# adapter.net
KiCad netlist of a schematic drawn in EAGLE
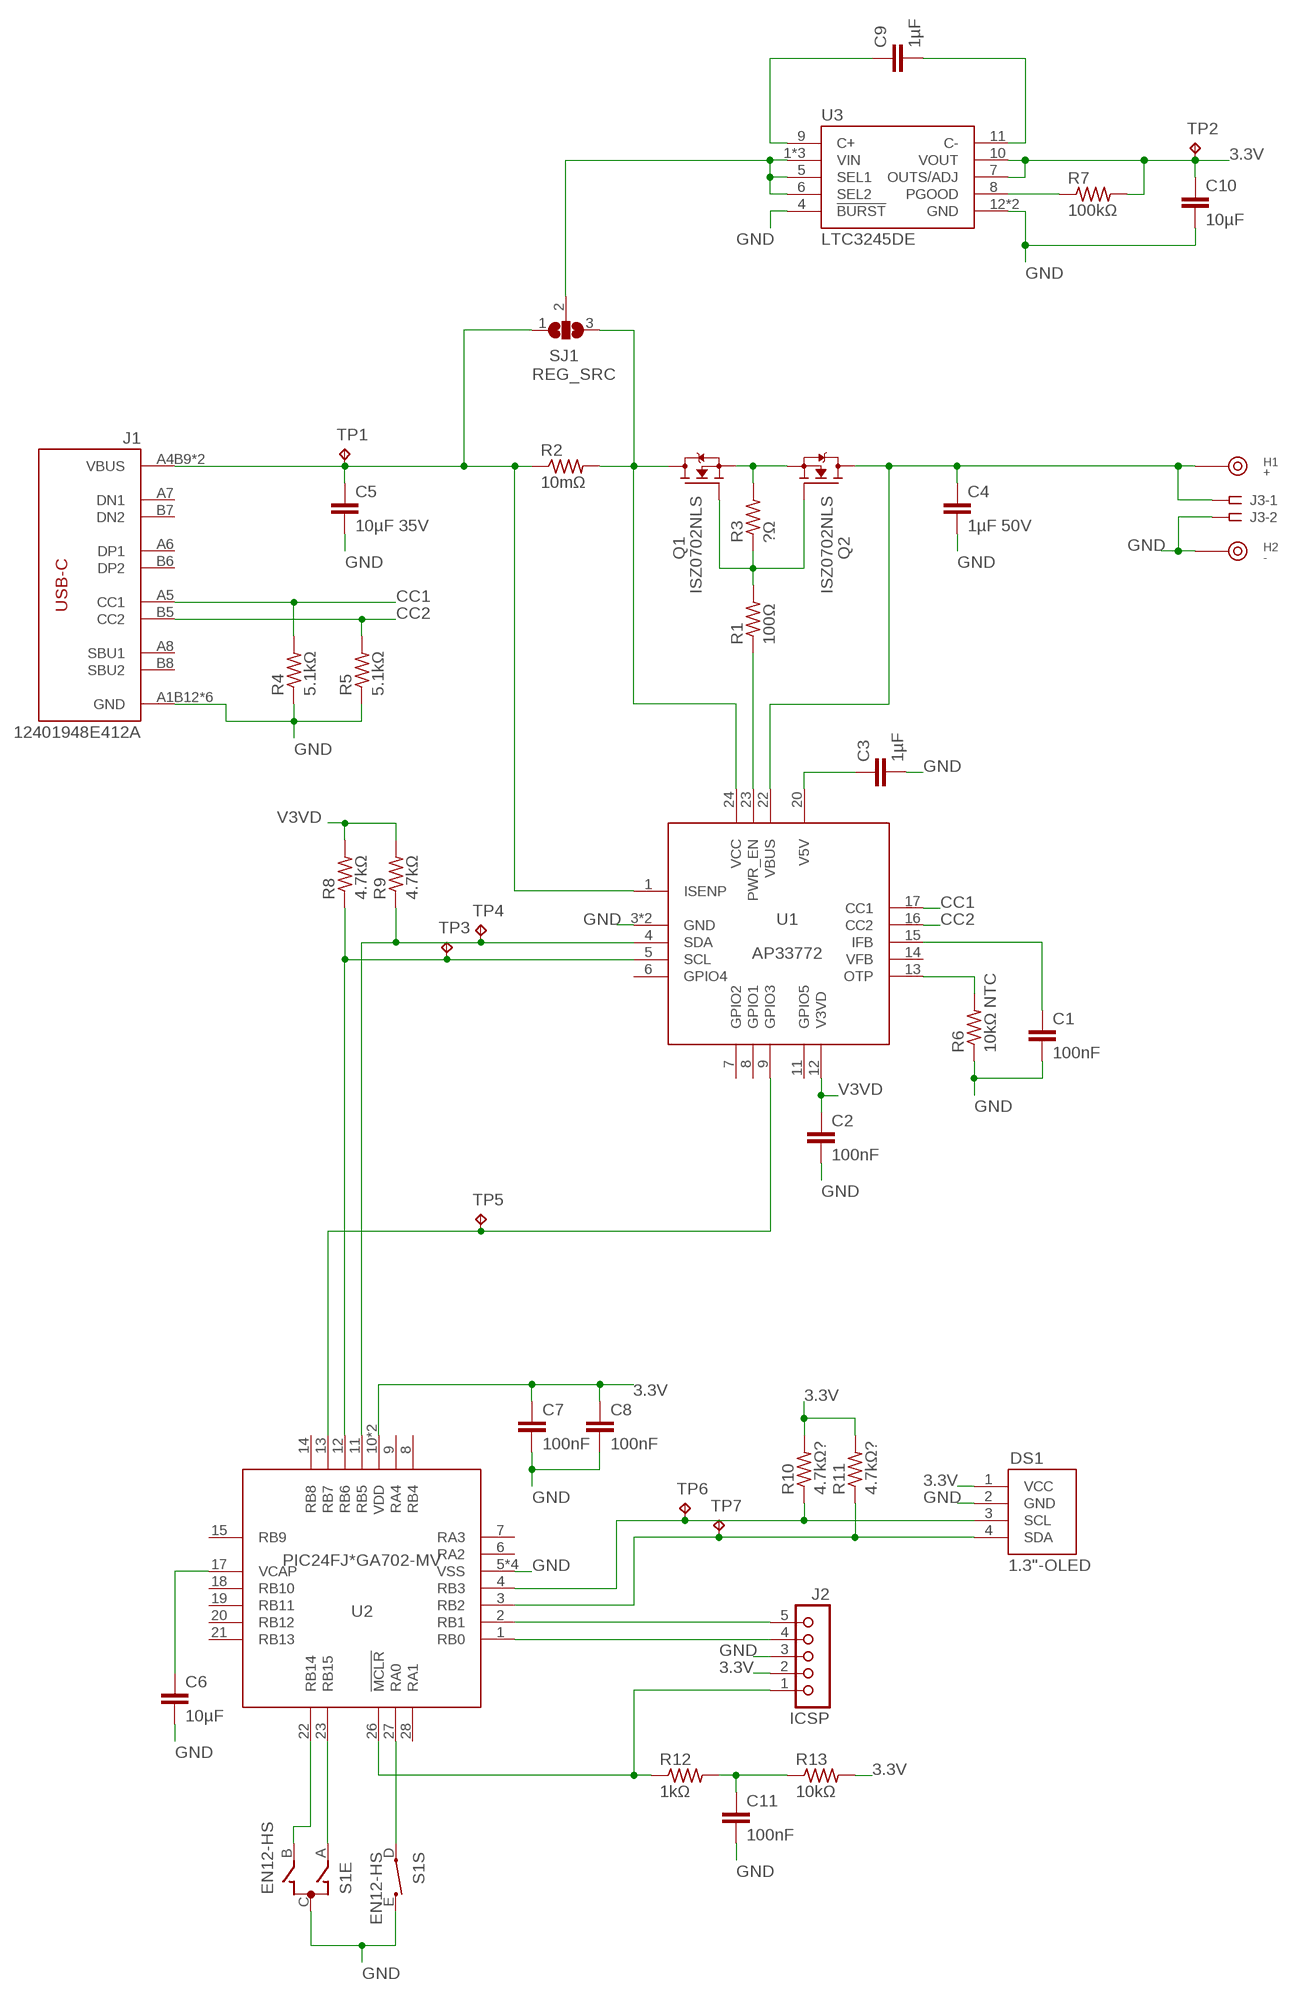
[diagram p0: schematic, sheet 1]

(export (version "E")
  (design (tool "Eeschema 10.0.6"))
  (components
    (comp (ref "C1")
      (value "100nF")
      (footprint "eagle-import:C0603")
      (libsource (lib "eagle-import") (part "C-EUC0603"))
    )
    (comp (ref "C2")
      (value "100nF")
      (footprint "eagle-import:C0603")
      (libsource (lib "eagle-import") (part "C-EUC0603"))
    )
    (comp (ref "C3")
      (value "1µF")
      (footprint "eagle-import:C0603")
      (libsource (lib "eagle-import") (part "C-EUC0603"))
    )
    (comp (ref "C4")
      (value "1µF 50V")
      (footprint "eagle-import:C0603")
      (libsource (lib "eagle-import") (part "C-EUC0603"))
    )
    (comp (ref "C5")
      (value "10µF 35V")
      (footprint "eagle-import:C1206")
      (libsource (lib "eagle-import") (part "C-EUC1206"))
    )
    (comp (ref "C6")
      (value "10µF")
      (footprint "eagle-import:C0805")
      (libsource (lib "eagle-import") (part "C-EUC0805"))
    )
    (comp (ref "C7")
      (value "100nF")
      (footprint "eagle-import:C0603")
      (libsource (lib "eagle-import") (part "C-EUC0603"))
    )
    (comp (ref "C8")
      (value "100nF")
      (footprint "eagle-import:C0603")
      (libsource (lib "eagle-import") (part "C-EUC0603"))
    )
    (comp (ref "C9")
      (value "1µF")
      (footprint "eagle-import:C0603")
      (libsource (lib "eagle-import") (part "C-EUC0603"))
    )
    (comp (ref "C10")
      (value "10µF")
      (footprint "eagle-import:C0805")
      (libsource (lib "eagle-import") (part "C-EUC0805"))
    )
    (comp (ref "C11")
      (value "100nF")
      (footprint "eagle-import:C0603")
      (libsource (lib "eagle-import") (part "C-EUC0603"))
    )
    (comp (ref "DS1")
      (value "1.3\"-OLED")
      (footprint "eagle-import:1.3_-OLED")
      (libsource (lib "eagle-import") (part "1.3{dblquote}-OLED"))
    )
    (comp (ref "H1")
      (value "+")
      (footprint "eagle-import:78614015360")
      (libsource (lib "eagle-import") (part "78614015360"))
    )
    (comp (ref "H2")
      (value "-")
      (footprint "eagle-import:78614015360")
      (libsource (lib "eagle-import") (part "78614015360"))
    )
    (comp (ref "J1")
      (value "12401948E412A")
      (footprint "eagle-import:12401948E412A")
      (libsource (lib "eagle-import") (part "12401948E412A"))
    )
    (comp (ref "J2")
      (value "ICSP")
      (footprint "eagle-import:5PIN-1.27")
      (libsource (lib "eagle-import") (part "5PIN-1.27"))
    )
    (comp (ref "J3")
      (value "SSW-102-02-G-S-RA")
      (footprint "eagle-import:SSW-102-02-G-S-RA")
      (fields (field (name "MF") "Samtec Inc."))
      (libsource (lib "eagle-import") (part "SSW-102-02-G-S-RA"))
    )
    (comp (ref "Q1")
      (value "ISZ0702NLS")
      (footprint "eagle-import:TSDSON-8")
      (libsource (lib "eagle-import") (part "TSDSON-8-N-MOSFET"))
    )
    (comp (ref "Q2")
      (value "ISZ0702NLS")
      (footprint "eagle-import:TSDSON-8")
      (libsource (lib "eagle-import") (part "TSDSON-8-N-MOSFET"))
    )
    (comp (ref "R1")
      (value "100Ω")
      (footprint "eagle-import:R0603")
      (libsource (lib "eagle-import") (part "R-US_R0603"))
    )
    (comp (ref "R2")
      (value "10mΩ")
      (footprint "eagle-import:R1206")
      (libsource (lib "eagle-import") (part "R-US_R1206"))
    )
    (comp (ref "R3")
      (value "?Ω")
      (footprint "eagle-import:R0603")
      (libsource (lib "eagle-import") (part "R-US_R0603"))
    )
    (comp (ref "R4")
      (value "5.1kΩ")
      (footprint "eagle-import:R0603")
      (libsource (lib "eagle-import") (part "R-US_R0603"))
    )
    (comp (ref "R5")
      (value "5.1kΩ")
      (footprint "eagle-import:R0603")
      (libsource (lib "eagle-import") (part "R-US_R0603"))
    )
    (comp (ref "R6")
      (value "10kΩ NTC")
      (footprint "eagle-import:R0603")
      (libsource (lib "eagle-import") (part "R-US_R0603"))
    )
    (comp (ref "R7")
      (value "100kΩ")
      (footprint "eagle-import:R0603")
      (libsource (lib "eagle-import") (part "R-US_R0603"))
    )
    (comp (ref "R8")
      (value "4.7kΩ")
      (footprint "eagle-import:R0603")
      (libsource (lib "eagle-import") (part "R-US_R0603"))
    )
    (comp (ref "R9")
      (value "4.7kΩ")
      (footprint "eagle-import:R0603")
      (libsource (lib "eagle-import") (part "R-US_R0603"))
    )
    (comp (ref "R10")
      (value "4.7kΩ?")
      (footprint "eagle-import:R0603")
      (libsource (lib "eagle-import") (part "R-US_R0603"))
    )
    (comp (ref "R11")
      (value "4.7kΩ?")
      (footprint "eagle-import:R0603")
      (libsource (lib "eagle-import") (part "R-US_R0603"))
    )
    (comp (ref "R12")
      (value "1kΩ")
      (footprint "eagle-import:R0603")
      (libsource (lib "eagle-import") (part "R-US_R0603"))
    )
    (comp (ref "R13")
      (value "10kΩ")
      (footprint "eagle-import:R0603")
      (libsource (lib "eagle-import") (part "R-US_R0603"))
    )
    (comp (ref "S1")
      (value "EN12-HS")
      (footprint "eagle-import:EN12-HS")
      (libsource (lib "eagle-import") (part "EN12-HS"))
    )
    (comp (ref "SJ1")
      (value "REG_SRC")
      (footprint "eagle-import:SJ_2")
      (libsource (lib "eagle-import") (part "SJ2W"))
    )
    (comp (ref "TP1")
      (value "RCU-0(J)")
      (footprint "eagle-import:TP_0603_JOINED")
      (libsource (lib "eagle-import") (part "RCU-0(J)"))
    )
    (comp (ref "TP2")
      (value "RCU-0(J)")
      (footprint "eagle-import:TP_0603_JOINED")
      (libsource (lib "eagle-import") (part "RCU-0(J)"))
    )
    (comp (ref "TP3")
      (value "RCU-0(J)")
      (footprint "eagle-import:TP_0603_JOINED")
      (libsource (lib "eagle-import") (part "RCU-0(J)"))
    )
    (comp (ref "TP4")
      (value "RCU-0(J)")
      (footprint "eagle-import:TP_0603_JOINED")
      (libsource (lib "eagle-import") (part "RCU-0(J)"))
    )
    (comp (ref "TP5")
      (value "RCU-0(J)")
      (footprint "eagle-import:TP_0603_JOINED")
      (libsource (lib "eagle-import") (part "RCU-0(J)"))
    )
    (comp (ref "TP6")
      (value "RCU-0(J)")
      (footprint "eagle-import:TP_0603_JOINED")
      (libsource (lib "eagle-import") (part "RCU-0(J)"))
    )
    (comp (ref "TP7")
      (value "RCU-0(J)")
      (footprint "eagle-import:TP_0603_JOINED")
      (libsource (lib "eagle-import") (part "RCU-0(J)"))
    )
    (comp (ref "U1")
      (value "AP33772")
      (footprint "eagle-import:QFN24-4X4")
      (libsource (lib "eagle-import") (part "AP33772"))
    )
    (comp (ref "U2")
      (value "PIC24FJ*GA702-MV")
      (footprint "eagle-import:UQFN28_4X4MM")
      (libsource (lib "eagle-import") (part "PIC24FJGA702-MV"))
    )
    (comp (ref "U3")
      (value "LTC3245DE")
      (footprint "eagle-import:DFN12")
      (libsource (lib "eagle-import") (part "LTC3245DE"))
    )
  )
  (nets
    (net (code "1") (name "/3.3V") (class "Default")
      (node (ref "C10") (pin "1") (pinfunction "1_1") (pintype "passive"))
      (node (ref "C7") (pin "1") (pinfunction "1_1") (pintype "passive"))
      (node (ref "C8") (pin "1") (pinfunction "1_1") (pintype "passive"))
      (node (ref "DS1") (pin "1") (pinfunction "VCC_1") (pintype "bidirectional"))
      (node (ref "J2") (pin "2") (pinfunction "2_2") (pintype "passive"))
      (node (ref "R10") (pin "2") (pinfunction "2_2") (pintype "passive"))
      (node (ref "R11") (pin "2") (pinfunction "2_2") (pintype "passive"))
      (node (ref "R13") (pin "2") (pinfunction "2_2") (pintype "passive"))
      (node (ref "R7") (pin "2") (pinfunction "2_2") (pintype "passive"))
      (node (ref "TP2") (pin "1") (pinfunction "TP_1") (pintype "input"))
      (node (ref "U2") (pin "10") (pinfunction "VDD_10") (pintype "bidirectional"))
      (node (ref "U2") (pin "25") (pinfunction "VDD_25") (pintype "bidirectional"))
      (node (ref "U3") (pin "10") (pinfunction "VOUT_10") (pintype "bidirectional"))
      (node (ref "U3") (pin "7") (pinfunction "OUTS/ADJ_7") (pintype "bidirectional"))
    )
    (net (code "2") (name "/CC1") (class "Default")
      (node (ref "J1") (pin "A5") (pinfunction "CC1_A5") (pintype "bidirectional"))
      (node (ref "R4") (pin "2") (pinfunction "2_2") (pintype "passive"))
      (node (ref "U1") (pin "17") (pinfunction "CC1_17") (pintype "bidirectional"))
    )
    (net (code "3") (name "/CC2") (class "Default")
      (node (ref "J1") (pin "B5") (pinfunction "CC2_B5") (pintype "bidirectional"))
      (node (ref "R5") (pin "2") (pinfunction "2_2") (pintype "passive"))
      (node (ref "U1") (pin "16") (pinfunction "CC2_16") (pintype "bidirectional"))
    )
    (net (code "4") (name "/GND") (class "Default")
      (node (ref "C1") (pin "2") (pinfunction "2_2") (pintype "passive"))
      (node (ref "C10") (pin "2") (pinfunction "2_2") (pintype "passive"))
      (node (ref "C11") (pin "2") (pinfunction "2_2") (pintype "passive"))
      (node (ref "C2") (pin "2") (pinfunction "2_2") (pintype "passive"))
      (node (ref "C3") (pin "2") (pinfunction "2_2") (pintype "passive"))
      (node (ref "C4") (pin "2") (pinfunction "2_2") (pintype "passive"))
      (node (ref "C5") (pin "2") (pinfunction "2_2") (pintype "passive"))
      (node (ref "C6") (pin "2") (pinfunction "2_2") (pintype "passive"))
      (node (ref "C7") (pin "2") (pinfunction "2_2") (pintype "passive"))
      (node (ref "C8") (pin "2") (pinfunction "2_2") (pintype "passive"))
      (node (ref "DS1") (pin "2") (pinfunction "GND_2") (pintype "bidirectional"))
      (node (ref "H2") (pin "M") (pinfunction "P$1_M") (pintype "bidirectional"))
      (node (ref "J1") (pin "A1B12") (pinfunction "GND_A1B12") (pintype "bidirectional"))
      (node (ref "J1") (pin "B1A12") (pinfunction "GND_B1A12") (pintype "bidirectional"))
      (node (ref "J1") (pin "M1") (pinfunction "GND_M1") (pintype "bidirectional"))
      (node (ref "J1") (pin "M2") (pinfunction "GND_M2") (pintype "bidirectional"))
      (node (ref "J1") (pin "M3") (pinfunction "GND_M3") (pintype "bidirectional"))
      (node (ref "J1") (pin "M4") (pinfunction "GND_M4") (pintype "bidirectional"))
      (node (ref "J2") (pin "3") (pinfunction "3_3") (pintype "passive"))
      (node (ref "J3") (pin "2") (pinfunction "1_2") (pintype "passive"))
      (node (ref "R4") (pin "1") (pinfunction "1_1") (pintype "passive"))
      (node (ref "R5") (pin "1") (pinfunction "1_1") (pintype "passive"))
      (node (ref "R6") (pin "1") (pinfunction "1_1") (pintype "passive"))
      (node (ref "S1") (pin "C") (pinfunction "C_C") (pintype "passive"))
      (node (ref "S1") (pin "E") (pinfunction "2_E") (pintype "passive"))
      (node (ref "U1") (pin "3") (pinfunction "GND_3") (pintype "bidirectional"))
      (node (ref "U1") (pin "EXP") (pinfunction "GND_EXP") (pintype "bidirectional"))
      (node (ref "U2") (pin "16") (pinfunction "VSS_16") (pintype "bidirectional"))
      (node (ref "U2") (pin "24") (pinfunction "VSS_24") (pintype "bidirectional"))
      (node (ref "U2") (pin "5") (pinfunction "VSS_5") (pintype "bidirectional"))
      (node (ref "U2") (pin "TH") (pinfunction "VSS_TH") (pintype "bidirectional"))
      (node (ref "U3") (pin "12") (pinfunction "GND_12") (pintype "bidirectional"))
      (node (ref "U3") (pin "4") (pinfunction "~{BURST}_4") (pintype "bidirectional"))
      (node (ref "U3") (pin "EXP") (pinfunction "GND_EXP") (pintype "bidirectional"))
    )
    (net (code "5") (name "/V3VD") (class "Default")
      (node (ref "C2") (pin "1") (pinfunction "1_1") (pintype "passive"))
      (node (ref "R8") (pin "2") (pinfunction "2_2") (pintype "passive"))
      (node (ref "R9") (pin "2") (pinfunction "2_2") (pintype "passive"))
      (node (ref "U1") (pin "12") (pinfunction "V3VD_12") (pintype "bidirectional"))
    )
    (net (code "6") (name "Net-(C11-Pad1)") (class "Default")
      (node (ref "C11") (pin "1") (pinfunction "1_1") (pintype "passive"))
      (node (ref "R12") (pin "2") (pinfunction "2_2") (pintype "passive"))
      (node (ref "R13") (pin "1") (pinfunction "1_1") (pintype "passive"))
    )
    (net (code "7") (name "Net-(DS1-SCL)") (class "Default")
      (node (ref "DS1") (pin "3") (pinfunction "SCL_3") (pintype "bidirectional"))
      (node (ref "R10") (pin "1") (pinfunction "1_1") (pintype "passive"))
      (node (ref "TP6") (pin "1") (pinfunction "TP_1") (pintype "input"))
      (node (ref "U2") (pin "4") (pinfunction "RB3_4") (pintype "bidirectional"))
    )
    (net (code "8") (name "Net-(DS1-SDA)") (class "Default")
      (node (ref "DS1") (pin "4") (pinfunction "SDA_4") (pintype "bidirectional"))
      (node (ref "R11") (pin "1") (pinfunction "1_1") (pintype "passive"))
      (node (ref "TP7") (pin "1") (pinfunction "TP_1") (pintype "input"))
      (node (ref "U2") (pin "3") (pinfunction "RB2_3") (pintype "bidirectional"))
    )
    (net (code "9") (name "Net-(H1-P$1)") (class "Default")
      (node (ref "C4") (pin "1") (pinfunction "1_1") (pintype "passive"))
      (node (ref "H1") (pin "M") (pinfunction "P$1_M") (pintype "bidirectional"))
      (node (ref "J3") (pin "1") (pinfunction "1_1") (pintype "passive"))
      (node (ref "Q2") (pin "5-8") (pinfunction "D_5-8") (pintype "passive"))
      (node (ref "U1") (pin "22") (pinfunction "VBUS_22") (pintype "bidirectional"))
    )
    (net (code "10") (name "Net-(Q1-D)") (class "Default")
      (node (ref "Q1") (pin "5-8") (pinfunction "D_5-8") (pintype "passive"))
      (node (ref "R2") (pin "2") (pinfunction "2_2") (pintype "passive"))
      (node (ref "SJ1") (pin "3") (pinfunction "3_3") (pintype "passive"))
      (node (ref "U1") (pin "24") (pinfunction "VCC_24") (pintype "bidirectional"))
    )
    (net (code "11") (name "Net-(Q1-G)") (class "Default")
      (node (ref "Q1") (pin "4") (pinfunction "G_4") (pintype "passive"))
      (node (ref "Q2") (pin "4") (pinfunction "G_4") (pintype "passive"))
      (node (ref "R1") (pin "2") (pinfunction "2_2") (pintype "passive"))
      (node (ref "R3") (pin "1") (pinfunction "1_1") (pintype "passive"))
    )
    (net (code "12") (name "Net-(Q1-S-Pad1)") (class "Default")
      (node (ref "Q1") (pin "1") (pinfunction "S_1") (pintype "passive"))
      (node (ref "Q1") (pin "2") (pinfunction "S_2") (pintype "passive"))
      (node (ref "Q1") (pin "3") (pinfunction "S_3") (pintype "passive"))
      (node (ref "Q2") (pin "1") (pinfunction "S_1") (pintype "passive"))
      (node (ref "Q2") (pin "2") (pinfunction "S_2") (pintype "passive"))
      (node (ref "Q2") (pin "3") (pinfunction "S_3") (pintype "passive"))
      (node (ref "R3") (pin "2") (pinfunction "2_2") (pintype "passive"))
    )
    (net (code "13") (name "Net-(S1B-1)") (class "Default")
      (node (ref "S1") (pin "D") (pinfunction "1_D") (pintype "passive"))
      (node (ref "U2") (pin "27") (pinfunction "RA0_27") (pintype "bidirectional"))
    )
    (net (code "14") (name "Net-(TP1-TP)") (class "Default")
      (node (ref "C5") (pin "1") (pinfunction "1_1") (pintype "passive"))
      (node (ref "J1") (pin "A4B9") (pinfunction "VBUS_A4B9") (pintype "bidirectional"))
      (node (ref "J1") (pin "B4A9") (pinfunction "VBUS_B4A9") (pintype "bidirectional"))
      (node (ref "R2") (pin "1") (pinfunction "1_1") (pintype "passive"))
      (node (ref "SJ1") (pin "1") (pinfunction "1_1") (pintype "passive"))
      (node (ref "TP1") (pin "1") (pinfunction "TP_1") (pintype "input"))
      (node (ref "U1") (pin "1") (pinfunction "ISENP_1") (pintype "bidirectional"))
    )
    (net (code "15") (name "Net-(TP3-TP)") (class "Default")
      (node (ref "R8") (pin "1") (pinfunction "1_1") (pintype "passive"))
      (node (ref "TP3") (pin "1") (pinfunction "TP_1") (pintype "input"))
      (node (ref "U1") (pin "5") (pinfunction "SCL_5") (pintype "bidirectional"))
      (node (ref "U2") (pin "12") (pinfunction "RB6_12") (pintype "bidirectional"))
    )
    (net (code "16") (name "Net-(TP4-TP)") (class "Default")
      (node (ref "R9") (pin "1") (pinfunction "1_1") (pintype "passive"))
      (node (ref "TP4") (pin "1") (pinfunction "TP_1") (pintype "input"))
      (node (ref "U1") (pin "4") (pinfunction "SDA_4") (pintype "bidirectional"))
      (node (ref "U2") (pin "11") (pinfunction "RB5_11") (pintype "bidirectional"))
    )
    (net (code "17") (name "Net-(TP5-TP)") (class "Default")
      (node (ref "TP5") (pin "1") (pinfunction "TP_1") (pintype "input"))
      (node (ref "U1") (pin "9") (pinfunction "GPIO3_9") (pintype "bidirectional"))
      (node (ref "U2") (pin "13") (pinfunction "RB7_13") (pintype "bidirectional"))
    )
    (net (code "18") (name "Net-(U1-IFB)") (class "Default")
      (node (ref "C1") (pin "1") (pinfunction "1_1") (pintype "passive"))
      (node (ref "U1") (pin "15") (pinfunction "IFB_15") (pintype "bidirectional"))
    )
    (net (code "19") (name "Net-(U1-OTP)") (class "Default")
      (node (ref "R6") (pin "2") (pinfunction "2_2") (pintype "passive"))
      (node (ref "U1") (pin "13") (pinfunction "OTP_13") (pintype "bidirectional"))
    )
    (net (code "20") (name "Net-(U1-PWR_EN)") (class "Default")
      (node (ref "R1") (pin "1") (pinfunction "1_1") (pintype "passive"))
      (node (ref "U1") (pin "23") (pinfunction "PWR_EN_23") (pintype "bidirectional"))
    )
    (net (code "21") (name "Net-(U1-V5V)") (class "Default")
      (node (ref "C3") (pin "1") (pinfunction "1_1") (pintype "passive"))
      (node (ref "U1") (pin "20") (pinfunction "V5V_20") (pintype "bidirectional"))
    )
    (net (code "22") (name "Net-(U2-RB0)") (class "Default")
      (node (ref "J2") (pin "4") (pinfunction "4_4") (pintype "passive"))
      (node (ref "U2") (pin "1") (pinfunction "RB0_1") (pintype "bidirectional"))
    )
    (net (code "23") (name "Net-(U2-RB1)") (class "Default")
      (node (ref "J2") (pin "5") (pinfunction "5_5") (pintype "passive"))
      (node (ref "U2") (pin "2") (pinfunction "RB1_2") (pintype "bidirectional"))
    )
    (net (code "24") (name "Net-(U2-RB14)") (class "Default")
      (node (ref "S1") (pin "B") (pinfunction "B_B") (pintype "passive"))
      (node (ref "U2") (pin "22") (pinfunction "RB14_22") (pintype "bidirectional"))
    )
    (net (code "25") (name "Net-(U2-RB15)") (class "Default")
      (node (ref "S1") (pin "A") (pinfunction "A_A") (pintype "passive"))
      (node (ref "U2") (pin "23") (pinfunction "RB15_23") (pintype "bidirectional"))
    )
    (net (code "26") (name "Net-(U2-VCAP)") (class "Default")
      (node (ref "C6") (pin "1") (pinfunction "1_1") (pintype "passive"))
      (node (ref "U2") (pin "17") (pinfunction "VCAP_17") (pintype "bidirectional"))
    )
    (net (code "27") (name "Net-(U2-~{MCLR})") (class "Default")
      (node (ref "J2") (pin "1") (pinfunction "1_1") (pintype "passive"))
      (node (ref "R12") (pin "1") (pinfunction "1_1") (pintype "passive"))
      (node (ref "U2") (pin "26") (pinfunction "~{MCLR}_26") (pintype "bidirectional"))
    )
    (net (code "28") (name "Net-(U3-C+)") (class "Default")
      (node (ref "C9") (pin "1") (pinfunction "1_1") (pintype "passive"))
      (node (ref "U3") (pin "9") (pinfunction "C+_9") (pintype "bidirectional"))
    )
    (net (code "29") (name "Net-(U3-C-)") (class "Default")
      (node (ref "C9") (pin "2") (pinfunction "2_2") (pintype "passive"))
      (node (ref "U3") (pin "11") (pinfunction "C-_11") (pintype "bidirectional"))
    )
    (net (code "30") (name "Net-(U3-PGOOD)") (class "Default")
      (node (ref "R7") (pin "1") (pinfunction "1_1") (pintype "passive"))
      (node (ref "U3") (pin "8") (pinfunction "PGOOD_8") (pintype "bidirectional"))
    )
    (net (code "31") (name "Net-(U3-SEL1)") (class "Default")
      (node (ref "SJ1") (pin "2") (pinfunction "2_2") (pintype "passive"))
      (node (ref "U3") (pin "1") (pinfunction "VIN_1") (pintype "bidirectional"))
      (node (ref "U3") (pin "2") (pinfunction "VIN_2") (pintype "bidirectional"))
      (node (ref "U3") (pin "3") (pinfunction "VIN_3") (pintype "bidirectional"))
      (node (ref "U3") (pin "5") (pinfunction "SEL1_5") (pintype "bidirectional"))
      (node (ref "U3") (pin "6") (pinfunction "SEL2_6") (pintype "bidirectional"))
    )
    (net (code "32") (name "unconnected-(J1-DN1-PadA7)") (class "Default")
      (node (ref "J1") (pin "A7") (pinfunction "DN1_A7") (pintype "bidirectional"))
    )
    (net (code "33") (name "unconnected-(J1-DN2-PadB7)") (class "Default")
      (node (ref "J1") (pin "B7") (pinfunction "DN2_B7") (pintype "bidirectional"))
    )
    (net (code "34") (name "unconnected-(J1-DP1-PadA6)") (class "Default")
      (node (ref "J1") (pin "A6") (pinfunction "DP1_A6") (pintype "bidirectional"))
    )
    (net (code "35") (name "unconnected-(J1-DP2-PadB6)") (class "Default")
      (node (ref "J1") (pin "B6") (pinfunction "DP2_B6") (pintype "bidirectional"))
    )
    (net (code "36") (name "unconnected-(J1-SBU1-PadA8)") (class "Default")
      (node (ref "J1") (pin "A8") (pinfunction "SBU1_A8") (pintype "bidirectional"))
    )
    (net (code "37") (name "unconnected-(J1-SBU2-PadB8)") (class "Default")
      (node (ref "J1") (pin "B8") (pinfunction "SBU2_B8") (pintype "bidirectional"))
    )
    (net (code "38") (name "unconnected-(U1-GPIO1-Pad8)") (class "Default")
      (node (ref "U1") (pin "8") (pinfunction "GPIO1_8") (pintype "bidirectional"))
    )
    (net (code "39") (name "unconnected-(U1-GPIO2-Pad7)") (class "Default")
      (node (ref "U1") (pin "7") (pinfunction "GPIO2_7") (pintype "bidirectional"))
    )
    (net (code "40") (name "unconnected-(U1-GPIO4-Pad6)") (class "Default")
      (node (ref "U1") (pin "6") (pinfunction "GPIO4_6") (pintype "bidirectional"))
    )
    (net (code "41") (name "unconnected-(U1-GPIO5-Pad11)") (class "Default")
      (node (ref "U1") (pin "11") (pinfunction "GPIO5_11") (pintype "bidirectional"))
    )
    (net (code "42") (name "unconnected-(U1-VFB-Pad14)") (class "Default")
      (node (ref "U1") (pin "14") (pinfunction "VFB_14") (pintype "bidirectional"))
    )
    (net (code "43") (name "unconnected-(U2-RA1-Pad28)") (class "Default")
      (node (ref "U2") (pin "28") (pinfunction "RA1_28") (pintype "bidirectional"))
    )
    (net (code "44") (name "unconnected-(U2-RA2-Pad6)") (class "Default")
      (node (ref "U2") (pin "6") (pinfunction "RA2_6") (pintype "bidirectional"))
    )
    (net (code "45") (name "unconnected-(U2-RA3-Pad7)") (class "Default")
      (node (ref "U2") (pin "7") (pinfunction "RA3_7") (pintype "bidirectional"))
    )
    (net (code "46") (name "unconnected-(U2-RA4-Pad9)") (class "Default")
      (node (ref "U2") (pin "9") (pinfunction "RA4_9") (pintype "bidirectional"))
    )
    (net (code "47") (name "unconnected-(U2-RB4-Pad8)") (class "Default")
      (node (ref "U2") (pin "8") (pinfunction "RB4_8") (pintype "bidirectional"))
    )
    (net (code "48") (name "unconnected-(U2-RB8-Pad14)") (class "Default")
      (node (ref "U2") (pin "14") (pinfunction "RB8_14") (pintype "bidirectional"))
    )
    (net (code "49") (name "unconnected-(U2-RB9-Pad15)") (class "Default")
      (node (ref "U2") (pin "15") (pinfunction "RB9_15") (pintype "bidirectional"))
    )
    (net (code "50") (name "unconnected-(U2-RB10-Pad18)") (class "Default")
      (node (ref "U2") (pin "18") (pinfunction "RB10_18") (pintype "bidirectional"))
    )
    (net (code "51") (name "unconnected-(U2-RB11-Pad19)") (class "Default")
      (node (ref "U2") (pin "19") (pinfunction "RB11_19") (pintype "bidirectional"))
    )
    (net (code "52") (name "unconnected-(U2-RB12-Pad20)") (class "Default")
      (node (ref "U2") (pin "20") (pinfunction "RB12_20") (pintype "bidirectional"))
    )
    (net (code "53") (name "unconnected-(U2-RB13-Pad21)") (class "Default")
      (node (ref "U2") (pin "21") (pinfunction "RB13_21") (pintype "bidirectional"))
    )
  )
)
